# board-a24-color.net
KiCad netlist of a schematic drawn in EasyEDA Pro
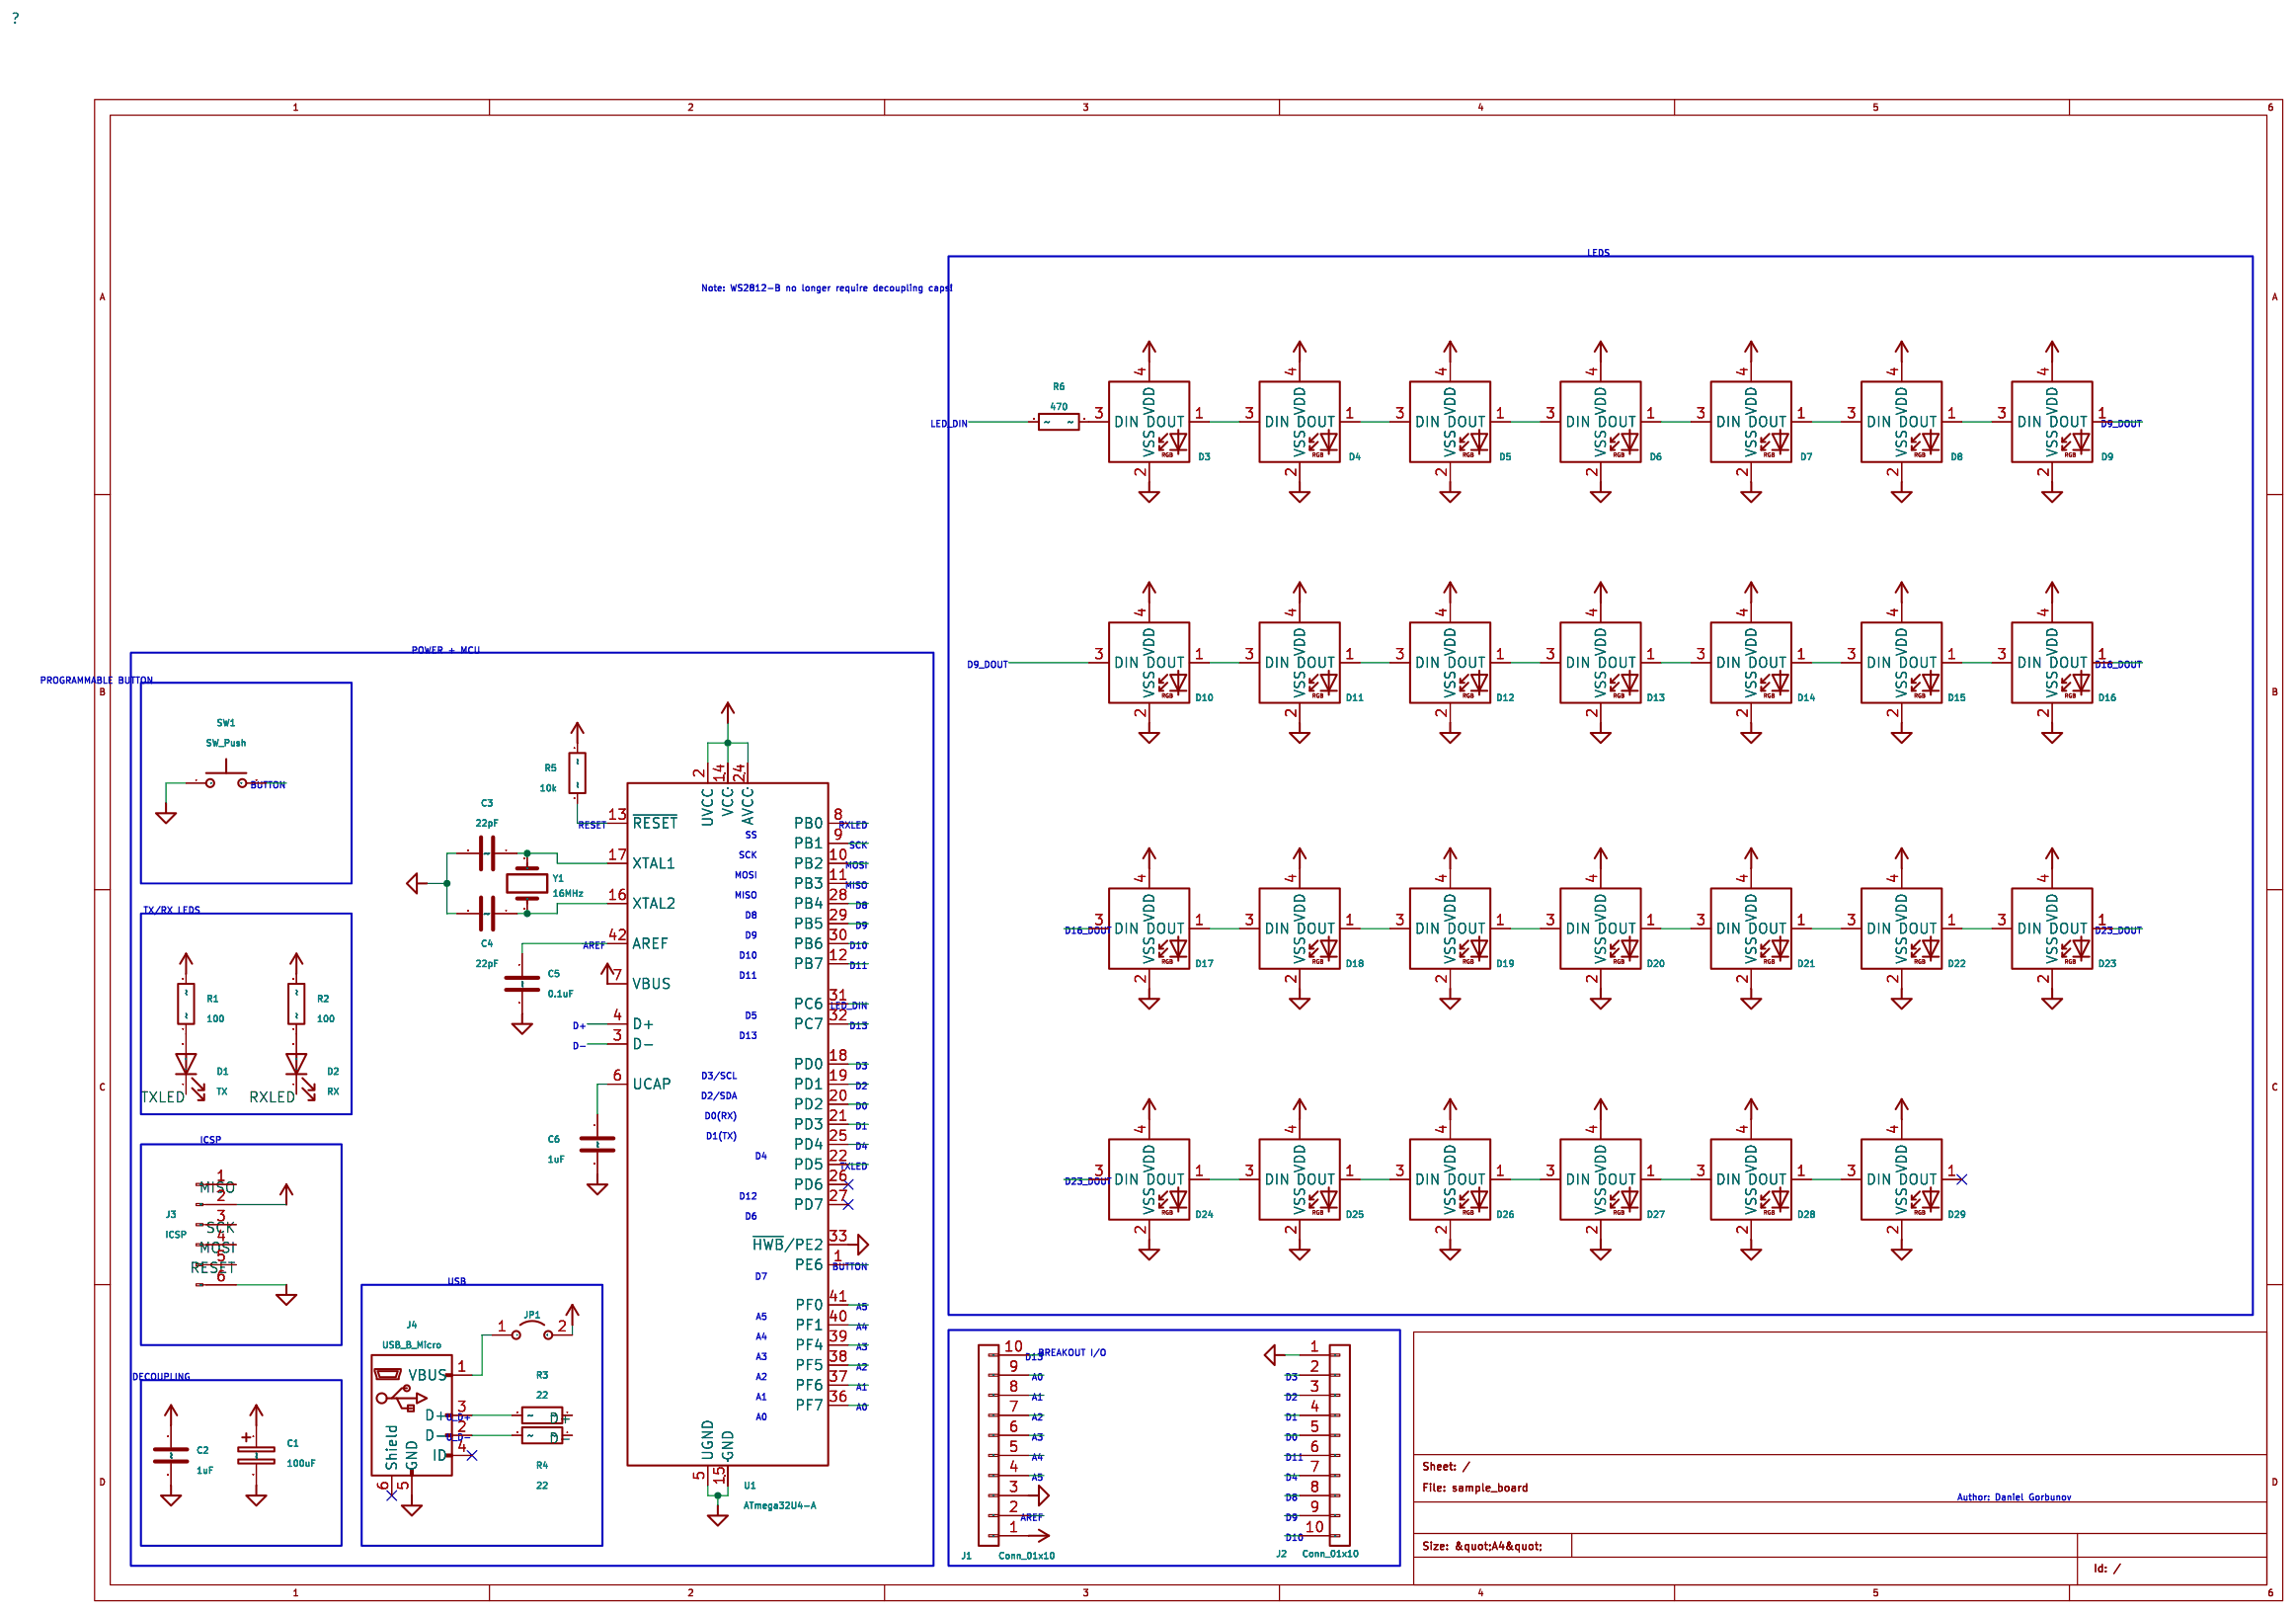
[diagram p0: schematic sheet]

(export (version "E")
  (design (tool "Eeschema 10.0.6"))
  (components
    (comp (ref "C1")
      (value "100uF")
      (footprint "easyedapro:Capacitor_SMD:CP_Elec_5x5.3")
      (libsource (lib "easyedapro") (part "Device_C_Polarized"))
    )
    (comp (ref "C2")
      (value "1uF")
      (footprint "easyedapro:Capacitor_SMD:C_0805_2012Metric_Pad1.18x1.45mm_HandSolder")
      (libsource (lib "easyedapro") (part "Device_C"))
    )
    (comp (ref "C3")
      (value "22pF")
      (footprint "easyedapro:Capacitor_SMD:C_0805_2012Metric_Pad1.18x1.45mm_HandSolder")
      (libsource (lib "easyedapro") (part "Device_C"))
    )
    (comp (ref "C4")
      (value "22pF")
      (footprint "easyedapro:Capacitor_SMD:C_0805_2012Metric_Pad1.18x1.45mm_HandSolder")
      (libsource (lib "easyedapro") (part "Device_C"))
    )
    (comp (ref "C5")
      (value "0.1uF")
      (footprint "easyedapro:Capacitor_SMD:C_0805_2012Metric_Pad1.18x1.45mm_HandSolder")
      (libsource (lib "easyedapro") (part "Device_C"))
    )
    (comp (ref "C6")
      (value "1uF")
      (footprint "easyedapro:Capacitor_SMD:C_0805_2012Metric_Pad1.18x1.45mm_HandSolder")
      (libsource (lib "easyedapro") (part "Device_C"))
    )
    (comp (ref "D1")
      (value "TX")
      (footprint "easyedapro:LED_SMD:LED_0805_2012Metric_Pad1.15x1.40mm_HandSolder")
      (libsource (lib "easyedapro") (part "Device_LED"))
    )
    (comp (ref "D2")
      (value "RX")
      (footprint "easyedapro:LED_SMD:LED_0805_2012Metric_Pad1.15x1.40mm_HandSolder")
      (libsource (lib "easyedapro") (part "Device_LED"))
    )
    (comp (ref "D3")
      (value "SK6812MINI")
      (footprint "easyedapro:LED_SMD:LED_SK6812MINI_PLCC4_3.5x3.5mm_P1.75mm")
      (libsource (lib "easyedapro") (part "LED_SK6812MINI"))
    )
    (comp (ref "D4")
      (value "SK6812MINI")
      (footprint "easyedapro:LED_SMD:LED_SK6812MINI_PLCC4_3.5x3.5mm_P1.75mm")
      (libsource (lib "easyedapro") (part "LED_SK6812MINI"))
    )
    (comp (ref "D5")
      (value "SK6812MINI")
      (footprint "easyedapro:LED_SMD:LED_SK6812MINI_PLCC4_3.5x3.5mm_P1.75mm")
      (libsource (lib "easyedapro") (part "LED_SK6812MINI"))
    )
    (comp (ref "D6")
      (value "SK6812MINI")
      (footprint "easyedapro:LED_SMD:LED_SK6812MINI_PLCC4_3.5x3.5mm_P1.75mm")
      (libsource (lib "easyedapro") (part "LED_SK6812MINI"))
    )
    (comp (ref "D7")
      (value "SK6812MINI")
      (footprint "easyedapro:LED_SMD:LED_SK6812MINI_PLCC4_3.5x3.5mm_P1.75mm")
      (libsource (lib "easyedapro") (part "LED_SK6812MINI"))
    )
    (comp (ref "D8")
      (value "SK6812MINI")
      (footprint "easyedapro:LED_SMD:LED_SK6812MINI_PLCC4_3.5x3.5mm_P1.75mm")
      (libsource (lib "easyedapro") (part "LED_SK6812MINI"))
    )
    (comp (ref "D9")
      (value "SK6812MINI")
      (footprint "easyedapro:LED_SMD:LED_SK6812MINI_PLCC4_3.5x3.5mm_P1.75mm")
      (libsource (lib "easyedapro") (part "LED_SK6812MINI"))
    )
    (comp (ref "D10")
      (value "SK6812MINI")
      (footprint "easyedapro:LED_SMD:LED_SK6812MINI_PLCC4_3.5x3.5mm_P1.75mm")
      (libsource (lib "easyedapro") (part "LED_SK6812MINI"))
    )
    (comp (ref "D11")
      (value "SK6812MINI")
      (footprint "easyedapro:LED_SMD:LED_SK6812MINI_PLCC4_3.5x3.5mm_P1.75mm")
      (libsource (lib "easyedapro") (part "LED_SK6812MINI"))
    )
    (comp (ref "D12")
      (value "SK6812MINI")
      (footprint "easyedapro:LED_SMD:LED_SK6812MINI_PLCC4_3.5x3.5mm_P1.75mm")
      (libsource (lib "easyedapro") (part "LED_SK6812MINI"))
    )
    (comp (ref "D13")
      (value "SK6812MINI")
      (footprint "easyedapro:LED_SMD:LED_SK6812MINI_PLCC4_3.5x3.5mm_P1.75mm")
      (libsource (lib "easyedapro") (part "LED_SK6812MINI"))
    )
    (comp (ref "D14")
      (value "SK6812MINI")
      (footprint "easyedapro:LED_SMD:LED_SK6812MINI_PLCC4_3.5x3.5mm_P1.75mm")
      (libsource (lib "easyedapro") (part "LED_SK6812MINI"))
    )
    (comp (ref "D15")
      (value "SK6812MINI")
      (footprint "easyedapro:LED_SMD:LED_SK6812MINI_PLCC4_3.5x3.5mm_P1.75mm")
      (libsource (lib "easyedapro") (part "LED_SK6812MINI"))
    )
    (comp (ref "D16")
      (value "SK6812MINI")
      (footprint "easyedapro:LED_SMD:LED_SK6812MINI_PLCC4_3.5x3.5mm_P1.75mm")
      (libsource (lib "easyedapro") (part "LED_SK6812MINI"))
    )
    (comp (ref "D17")
      (value "SK6812MINI")
      (footprint "easyedapro:LED_SMD:LED_SK6812MINI_PLCC4_3.5x3.5mm_P1.75mm")
      (libsource (lib "easyedapro") (part "LED_SK6812MINI"))
    )
    (comp (ref "D18")
      (value "SK6812MINI")
      (footprint "easyedapro:LED_SMD:LED_SK6812MINI_PLCC4_3.5x3.5mm_P1.75mm")
      (libsource (lib "easyedapro") (part "LED_SK6812MINI"))
    )
    (comp (ref "D19")
      (value "SK6812MINI")
      (footprint "easyedapro:LED_SMD:LED_SK6812MINI_PLCC4_3.5x3.5mm_P1.75mm")
      (libsource (lib "easyedapro") (part "LED_SK6812MINI"))
    )
    (comp (ref "D20")
      (value "SK6812MINI")
      (footprint "easyedapro:LED_SMD:LED_SK6812MINI_PLCC4_3.5x3.5mm_P1.75mm")
      (libsource (lib "easyedapro") (part "LED_SK6812MINI"))
    )
    (comp (ref "D21")
      (value "SK6812MINI")
      (footprint "easyedapro:LED_SMD:LED_SK6812MINI_PLCC4_3.5x3.5mm_P1.75mm")
      (libsource (lib "easyedapro") (part "LED_SK6812MINI"))
    )
    (comp (ref "D22")
      (value "SK6812MINI")
      (footprint "easyedapro:LED_SMD:LED_SK6812MINI_PLCC4_3.5x3.5mm_P1.75mm")
      (libsource (lib "easyedapro") (part "LED_SK6812MINI"))
    )
    (comp (ref "D23")
      (value "SK6812MINI")
      (footprint "easyedapro:LED_SMD:LED_SK6812MINI_PLCC4_3.5x3.5mm_P1.75mm")
      (libsource (lib "easyedapro") (part "LED_SK6812MINI"))
    )
    (comp (ref "D24")
      (value "SK6812MINI")
      (footprint "easyedapro:LED_SMD:LED_SK6812MINI_PLCC4_3.5x3.5mm_P1.75mm")
      (libsource (lib "easyedapro") (part "LED_SK6812MINI"))
    )
    (comp (ref "D25")
      (value "SK6812MINI")
      (footprint "easyedapro:LED_SMD:LED_SK6812MINI_PLCC4_3.5x3.5mm_P1.75mm")
      (libsource (lib "easyedapro") (part "LED_SK6812MINI"))
    )
    (comp (ref "D26")
      (value "SK6812MINI")
      (footprint "easyedapro:LED_SMD:LED_SK6812MINI_PLCC4_3.5x3.5mm_P1.75mm")
      (libsource (lib "easyedapro") (part "LED_SK6812MINI"))
    )
    (comp (ref "D27")
      (value "SK6812MINI")
      (footprint "easyedapro:LED_SMD:LED_SK6812MINI_PLCC4_3.5x3.5mm_P1.75mm")
      (libsource (lib "easyedapro") (part "LED_SK6812MINI"))
    )
    (comp (ref "D28")
      (value "SK6812MINI")
      (footprint "easyedapro:LED_SMD:LED_SK6812MINI_PLCC4_3.5x3.5mm_P1.75mm")
      (libsource (lib "easyedapro") (part "LED_SK6812MINI"))
    )
    (comp (ref "D29")
      (value "SK6812MINI")
      (footprint "easyedapro:LED_SMD:LED_SK6812MINI_PLCC4_3.5x3.5mm_P1.75mm")
      (libsource (lib "easyedapro") (part "LED_SK6812MINI"))
    )
    (comp (ref "J1")
      (value "Conn_01x10")
      (footprint "easyedapro:Connector_PinHeader_2.54mm:PinHeader_1x10_P2.54mm_Vertical")
      (libsource (lib "easyedapro") (part "Connector_Generic_Conn_01x10"))
    )
    (comp (ref "J2")
      (value "Conn_01x10")
      (footprint "easyedapro:Connector_PinHeader_2.54mm:PinHeader_1x10_P2.54mm_Vertical")
      (libsource (lib "easyedapro") (part "Connector_Generic_Conn_01x10"))
    )
    (comp (ref "J3")
      (value "ICSP")
      (footprint "easyedapro:Connector_PinHeader_2.54mm:PinHeader_2x03_P2.54mm_Vertical")
      (libsource (lib "easyedapro") (part "Connector_Conn_01x06_Pin"))
    )
    (comp (ref "J4")
      (value "USB_B_Micro")
      (footprint "easyedapro:Connector_USB:USB_Micro-B_GCT_USB3076-30-A")
      (libsource (lib "easyedapro") (part "Connector_USB_B_Micro"))
    )
    (comp (ref "JP1")
      (value "Jumper_2_Open")
      (footprint "easyedapro:Jumper:SolderJumper-2_P1.3mm_Open_TrianglePad1.0x1.5mm")
      (libsource (lib "easyedapro") (part "Jumper_Jumper_2_Open"))
    )
    (comp (ref "R1")
      (value "100")
      (footprint "easyedapro:Resistor_SMD:R_0805_2012Metric_Pad1.20x1.40mm_HandSolder")
      (libsource (lib "easyedapro") (part "Device_R"))
    )
    (comp (ref "R2")
      (value "100")
      (footprint "easyedapro:Resistor_SMD:R_0805_2012Metric_Pad1.20x1.40mm_HandSolder")
      (libsource (lib "easyedapro") (part "Device_R"))
    )
    (comp (ref "R3")
      (value "22")
      (footprint "easyedapro:Resistor_SMD:R_0805_2012Metric_Pad1.20x1.40mm_HandSolder")
      (libsource (lib "easyedapro") (part "Device_R"))
    )
    (comp (ref "R4")
      (value "22")
      (footprint "easyedapro:Resistor_SMD:R_0805_2012Metric_Pad1.20x1.40mm_HandSolder")
      (libsource (lib "easyedapro") (part "Device_R"))
    )
    (comp (ref "R5")
      (value "10k")
      (footprint "easyedapro:Resistor_SMD:R_0805_2012Metric_Pad1.20x1.40mm_HandSolder")
      (libsource (lib "easyedapro") (part "Device_R"))
    )
    (comp (ref "R6")
      (value "470")
      (footprint "easyedapro:Resistor_SMD:R_0805_2012Metric_Pad1.20x1.40mm_HandSolder")
      (libsource (lib "easyedapro") (part "Device_R"))
    )
    (comp (ref "SW1")
      (value "SW_Push")
      (footprint "easyedapro:Button_Switch_SMD:SW_SPST_PTS647_Sx38")
      (description "Push button switch, generic, two pins")
      (libsource (lib "easyedapro") (part "Switch_SW_Push"))
    )
    (comp (ref "U1")
      (value "ATmega32U4-A")
      (footprint "easyedapro:Package_QFP:TQFP-44_10x10mm_P0.8mm")
      (libsource (lib "easyedapro") (part "MCU_Microchip_ATmega_ATmega32U4-A"))
    )
    (comp (ref "Y1")
      (value "16MHz")
      (footprint "easyedapro:Crystal:Crystal_SMD_5032-2Pin_5.0x3.2mm")
      (libsource (lib "easyedapro") (part "Device_Crystal"))
    )
  )
  (nets
    (net (code "1") (name "/A0") (class "Default")
      (node (ref "J1") (pin "9") (pinfunction "Pin_9_9") (pintype "unspecified"))
      (node (ref "U1") (pin "36") (pinfunction "PF7_36") (pintype "bidirectional"))
    )
    (net (code "2") (name "/A1") (class "Default")
      (node (ref "J1") (pin "8") (pinfunction "Pin_8_8") (pintype "unspecified"))
      (node (ref "U1") (pin "37") (pinfunction "PF6_37") (pintype "bidirectional"))
    )
    (net (code "3") (name "/A2") (class "Default")
      (node (ref "J1") (pin "7") (pinfunction "Pin_7_7") (pintype "unspecified"))
      (node (ref "U1") (pin "38") (pinfunction "PF5_38") (pintype "bidirectional"))
    )
    (net (code "4") (name "/A3") (class "Default")
      (node (ref "J1") (pin "6") (pinfunction "Pin_6_6") (pintype "unspecified"))
      (node (ref "U1") (pin "39") (pinfunction "PF4_39") (pintype "bidirectional"))
    )
    (net (code "5") (name "/A4") (class "Default")
      (node (ref "J1") (pin "5") (pinfunction "Pin_5_5") (pintype "unspecified"))
      (node (ref "U1") (pin "40") (pinfunction "PF1_40") (pintype "bidirectional"))
    )
    (net (code "6") (name "/A5") (class "Default")
      (node (ref "J1") (pin "4") (pinfunction "Pin_4_4") (pintype "unspecified"))
      (node (ref "U1") (pin "41") (pinfunction "PF0_41") (pintype "bidirectional"))
    )
    (net (code "7") (name "/AREF") (class "Default")
      (node (ref "C5") (pin "1") (pinfunction "~_1") (pintype "unspecified"))
      (node (ref "J1") (pin "2") (pinfunction "Pin_2_2") (pintype "unspecified"))
      (node (ref "U1") (pin "42") (pinfunction "AREF_42") (pintype "unspecified"))
    )
    (net (code "8") (name "/BUTTON") (class "Default")
      (node (ref "SW1") (pin "2") (pinfunction "2_2") (pintype "unspecified"))
      (node (ref "U1") (pin "1") (pinfunction "PE6_1") (pintype "bidirectional"))
    )
    (net (code "9") (name "/D+") (class "Default")
      (node (ref "R3") (pin "1") (pinfunction "~_1") (pintype "unspecified"))
      (node (ref "U1") (pin "4") (pinfunction "D+_4") (pintype "bidirectional"))
    )
    (net (code "10") (name "/D-") (class "Default")
      (node (ref "R4") (pin "1") (pinfunction "~_1") (pintype "unspecified"))
      (node (ref "U1") (pin "3") (pinfunction "D-_3") (pintype "bidirectional"))
    )
    (net (code "11") (name "/D0") (class "Default")
      (node (ref "J2") (pin "5") (pinfunction "Pin_5_5") (pintype "unspecified"))
      (node (ref "U1") (pin "20") (pinfunction "PD2_20") (pintype "bidirectional"))
    )
    (net (code "12") (name "/D1") (class "Default")
      (node (ref "J2") (pin "4") (pinfunction "Pin_4_4") (pintype "unspecified"))
      (node (ref "U1") (pin "21") (pinfunction "PD3_21") (pintype "bidirectional"))
    )
    (net (code "13") (name "/D2") (class "Default")
      (node (ref "J2") (pin "3") (pinfunction "Pin_3_3") (pintype "unspecified"))
      (node (ref "U1") (pin "19") (pinfunction "PD1_19") (pintype "bidirectional"))
    )
    (net (code "14") (name "/D3") (class "Default")
      (node (ref "J2") (pin "2") (pinfunction "Pin_2_2") (pintype "unspecified"))
      (node (ref "U1") (pin "18") (pinfunction "PD0_18") (pintype "bidirectional"))
    )
    (net (code "15") (name "/D4") (class "Default")
      (node (ref "J2") (pin "7") (pinfunction "Pin_7_7") (pintype "unspecified"))
      (node (ref "U1") (pin "25") (pinfunction "PD4_25") (pintype "bidirectional"))
    )
    (net (code "16") (name "/D8") (class "Default")
      (node (ref "J2") (pin "8") (pinfunction "Pin_8_8") (pintype "unspecified"))
      (node (ref "U1") (pin "28") (pinfunction "PB4_28") (pintype "bidirectional"))
    )
    (net (code "17") (name "/D9") (class "Default")
      (node (ref "J2") (pin "9") (pinfunction "Pin_9_9") (pintype "unspecified"))
      (node (ref "U1") (pin "29") (pinfunction "PB5_29") (pintype "bidirectional"))
    )
    (net (code "18") (name "/D9_DOUT") (class "Default")
      (node (ref "D10") (pin "3") (pinfunction "DIN_3") (pintype "input"))
      (node (ref "D9") (pin "1") (pinfunction "DOUT_1") (pintype "output"))
    )
    (net (code "19") (name "/D10") (class "Default")
      (node (ref "J2") (pin "10") (pinfunction "Pin_10_10") (pintype "unspecified"))
      (node (ref "U1") (pin "30") (pinfunction "PB6_30") (pintype "bidirectional"))
    )
    (net (code "20") (name "/D11") (class "Default")
      (node (ref "J2") (pin "6") (pinfunction "Pin_6_6") (pintype "unspecified"))
      (node (ref "U1") (pin "12") (pinfunction "PB7_12") (pintype "bidirectional"))
    )
    (net (code "21") (name "/D13") (class "Default")
      (node (ref "J1") (pin "10") (pinfunction "Pin_10_10") (pintype "unspecified"))
      (node (ref "U1") (pin "32") (pinfunction "PC7_32") (pintype "bidirectional"))
    )
    (net (code "22") (name "/D16_DOUT") (class "Default")
      (node (ref "D16") (pin "1") (pinfunction "DOUT_1") (pintype "output"))
      (node (ref "D17") (pin "3") (pinfunction "DIN_3") (pintype "input"))
    )
    (net (code "23") (name "/D23_DOUT") (class "Default")
      (node (ref "D23") (pin "1") (pinfunction "DOUT_1") (pintype "output"))
      (node (ref "D24") (pin "3") (pinfunction "DIN_3") (pintype "input"))
    )
    (net (code "24") (name "/LED_DIN") (class "Default")
      (node (ref "R6") (pin "1") (pinfunction "~_1") (pintype "unspecified"))
      (node (ref "U1") (pin "31") (pinfunction "PC6_31") (pintype "bidirectional"))
    )
    (net (code "25") (name "/MISO") (class "Default")
      (node (ref "J3") (pin "1") (pinfunction "Pin_1_1") (pintype "unspecified"))
      (node (ref "U1") (pin "11") (pinfunction "PB3_11") (pintype "bidirectional"))
    )
    (net (code "26") (name "/MOSI") (class "Default")
      (node (ref "J3") (pin "4") (pinfunction "Pin_4_4") (pintype "unspecified"))
      (node (ref "U1") (pin "10") (pinfunction "PB2_10") (pintype "bidirectional"))
    )
    (net (code "27") (name "/RESET") (class "Default")
      (node (ref "J3") (pin "5") (pinfunction "Pin_5_5") (pintype "unspecified"))
      (node (ref "R5") (pin "2") (pinfunction "~_2") (pintype "unspecified"))
      (node (ref "U1") (pin "13") (pinfunction "~{RESET}_13") (pintype "input"))
    )
    (net (code "28") (name "/RXLED") (class "Default")
      (node (ref "D2") (pin "1") (pinfunction "K_1") (pintype "unspecified"))
      (node (ref "U1") (pin "8") (pinfunction "PB0_8") (pintype "bidirectional"))
    )
    (net (code "29") (name "/SCK") (class "Default")
      (node (ref "J3") (pin "3") (pinfunction "Pin_3_3") (pintype "unspecified"))
      (node (ref "U1") (pin "9") (pinfunction "PB1_9") (pintype "bidirectional"))
    )
    (net (code "30") (name "/TXLED") (class "Default")
      (node (ref "D1") (pin "1") (pinfunction "K_1") (pintype "unspecified"))
      (node (ref "U1") (pin "22") (pinfunction "PD5_22") (pintype "bidirectional"))
    )
    (net (code "31") (name "/U_D+") (class "Default")
      (node (ref "J4") (pin "3") (pinfunction "D+_3") (pintype "bidirectional"))
      (node (ref "R3") (pin "2") (pinfunction "~_2") (pintype "unspecified"))
    )
    (net (code "32") (name "/U_D-") (class "Default")
      (node (ref "J4") (pin "2") (pinfunction "D-_2") (pintype "bidirectional"))
      (node (ref "R4") (pin "2") (pinfunction "~_2") (pintype "unspecified"))
    )
    (net (code "33") (name "Net-(D1-A)") (class "Default")
      (node (ref "D1") (pin "2") (pinfunction "A_2") (pintype "unspecified"))
      (node (ref "R1") (pin "1") (pinfunction "~_1") (pintype "unspecified"))
    )
    (net (code "34") (name "Net-(D2-A)") (class "Default")
      (node (ref "D2") (pin "2") (pinfunction "A_2") (pintype "unspecified"))
      (node (ref "R2") (pin "1") (pinfunction "~_1") (pintype "unspecified"))
    )
    (net (code "35") (name "Net-(D3-DIN)") (class "Default")
      (node (ref "D3") (pin "3") (pinfunction "DIN_3") (pintype "input"))
      (node (ref "R6") (pin "2") (pinfunction "~_2") (pintype "unspecified"))
    )
    (net (code "36") (name "Net-(D3-DOUT)") (class "Default")
      (node (ref "D3") (pin "1") (pinfunction "DOUT_1") (pintype "output"))
      (node (ref "D4") (pin "3") (pinfunction "DIN_3") (pintype "input"))
    )
    (net (code "37") (name "Net-(D4-DOUT)") (class "Default")
      (node (ref "D4") (pin "1") (pinfunction "DOUT_1") (pintype "output"))
      (node (ref "D5") (pin "3") (pinfunction "DIN_3") (pintype "input"))
    )
    (net (code "38") (name "Net-(D5-DOUT)") (class "Default")
      (node (ref "D5") (pin "1") (pinfunction "DOUT_1") (pintype "output"))
      (node (ref "D6") (pin "3") (pinfunction "DIN_3") (pintype "input"))
    )
    (net (code "39") (name "Net-(D6-DOUT)") (class "Default")
      (node (ref "D6") (pin "1") (pinfunction "DOUT_1") (pintype "output"))
      (node (ref "D7") (pin "3") (pinfunction "DIN_3") (pintype "input"))
    )
    (net (code "40") (name "Net-(D7-DOUT)") (class "Default")
      (node (ref "D7") (pin "1") (pinfunction "DOUT_1") (pintype "output"))
      (node (ref "D8") (pin "3") (pinfunction "DIN_3") (pintype "input"))
    )
    (net (code "41") (name "Net-(D8-DOUT)") (class "Default")
      (node (ref "D8") (pin "1") (pinfunction "DOUT_1") (pintype "output"))
      (node (ref "D9") (pin "3") (pinfunction "DIN_3") (pintype "input"))
    )
    (net (code "42") (name "Net-(D10-DOUT)") (class "Default")
      (node (ref "D10") (pin "1") (pinfunction "DOUT_1") (pintype "output"))
      (node (ref "D11") (pin "3") (pinfunction "DIN_3") (pintype "input"))
    )
    (net (code "43") (name "Net-(D11-DOUT)") (class "Default")
      (node (ref "D11") (pin "1") (pinfunction "DOUT_1") (pintype "output"))
      (node (ref "D12") (pin "3") (pinfunction "DIN_3") (pintype "input"))
    )
    (net (code "44") (name "Net-(D12-DOUT)") (class "Default")
      (node (ref "D12") (pin "1") (pinfunction "DOUT_1") (pintype "output"))
      (node (ref "D13") (pin "3") (pinfunction "DIN_3") (pintype "input"))
    )
    (net (code "45") (name "Net-(D13-DOUT)") (class "Default")
      (node (ref "D13") (pin "1") (pinfunction "DOUT_1") (pintype "output"))
      (node (ref "D14") (pin "3") (pinfunction "DIN_3") (pintype "input"))
    )
    (net (code "46") (name "Net-(D14-DOUT)") (class "Default")
      (node (ref "D14") (pin "1") (pinfunction "DOUT_1") (pintype "output"))
      (node (ref "D15") (pin "3") (pinfunction "DIN_3") (pintype "input"))
    )
    (net (code "47") (name "Net-(D15-DOUT)") (class "Default")
      (node (ref "D15") (pin "1") (pinfunction "DOUT_1") (pintype "output"))
      (node (ref "D16") (pin "3") (pinfunction "DIN_3") (pintype "input"))
    )
    (net (code "48") (name "Net-(D17-DOUT)") (class "Default")
      (node (ref "D17") (pin "1") (pinfunction "DOUT_1") (pintype "output"))
      (node (ref "D18") (pin "3") (pinfunction "DIN_3") (pintype "input"))
    )
    (net (code "49") (name "Net-(D18-DOUT)") (class "Default")
      (node (ref "D18") (pin "1") (pinfunction "DOUT_1") (pintype "output"))
      (node (ref "D19") (pin "3") (pinfunction "DIN_3") (pintype "input"))
    )
    (net (code "50") (name "Net-(D19-DOUT)") (class "Default")
      (node (ref "D19") (pin "1") (pinfunction "DOUT_1") (pintype "output"))
      (node (ref "D20") (pin "3") (pinfunction "DIN_3") (pintype "input"))
    )
    (net (code "51") (name "Net-(D20-DOUT)") (class "Default")
      (node (ref "D20") (pin "1") (pinfunction "DOUT_1") (pintype "output"))
      (node (ref "D21") (pin "3") (pinfunction "DIN_3") (pintype "input"))
    )
    (net (code "52") (name "Net-(D21-DOUT)") (class "Default")
      (node (ref "D21") (pin "1") (pinfunction "DOUT_1") (pintype "output"))
      (node (ref "D22") (pin "3") (pinfunction "DIN_3") (pintype "input"))
    )
    (net (code "53") (name "Net-(D22-DOUT)") (class "Default")
      (node (ref "D22") (pin "1") (pinfunction "DOUT_1") (pintype "output"))
      (node (ref "D23") (pin "3") (pinfunction "DIN_3") (pintype "input"))
    )
    (net (code "54") (name "Net-(D24-DOUT)") (class "Default")
      (node (ref "D24") (pin "1") (pinfunction "DOUT_1") (pintype "output"))
      (node (ref "D25") (pin "3") (pinfunction "DIN_3") (pintype "input"))
    )
    (net (code "55") (name "Net-(D25-DOUT)") (class "Default")
      (node (ref "D25") (pin "1") (pinfunction "DOUT_1") (pintype "output"))
      (node (ref "D26") (pin "3") (pinfunction "DIN_3") (pintype "input"))
    )
    (net (code "56") (name "Net-(D26-DOUT)") (class "Default")
      (node (ref "D26") (pin "1") (pinfunction "DOUT_1") (pintype "output"))
      (node (ref "D27") (pin "3") (pinfunction "DIN_3") (pintype "input"))
    )
    (net (code "57") (name "Net-(D27-DOUT)") (class "Default")
      (node (ref "D27") (pin "1") (pinfunction "DOUT_1") (pintype "output"))
      (node (ref "D28") (pin "3") (pinfunction "DIN_3") (pintype "input"))
    )
    (net (code "58") (name "Net-(D28-DOUT)") (class "Default")
      (node (ref "D28") (pin "1") (pinfunction "DOUT_1") (pintype "output"))
      (node (ref "D29") (pin "3") (pinfunction "DIN_3") (pintype "input"))
    )
    (net (code "59") (name "Net-(J4-VBUS)") (class "Default")
      (node (ref "J4") (pin "1") (pinfunction "VBUS_1") (pintype "unspecified"))
      (node (ref "JP1") (pin "1") (pinfunction "A_1") (pintype "unspecified"))
    )
    (net (code "60") (name "Net-(U1-UCAP)") (class "Default")
      (node (ref "C6") (pin "1") (pinfunction "~_1") (pintype "unspecified"))
      (node (ref "U1") (pin "6") (pinfunction "UCAP_6") (pintype "unspecified"))
    )
    (net (code "61") (name "Net-(U1-XTAL1)") (class "Default")
      (node (ref "C3") (pin "1") (pinfunction "~_1") (pintype "unspecified"))
      (node (ref "U1") (pin "17") (pinfunction "XTAL1_17") (pintype "input"))
      (node (ref "Y1") (pin "1") (pinfunction "1_1") (pintype "unspecified"))
    )
    (net (code "62") (name "Net-(U1-XTAL2)") (class "Default")
      (node (ref "C4") (pin "1") (pinfunction "~_1") (pintype "unspecified"))
      (node (ref "U1") (pin "16") (pinfunction "XTAL2_16") (pintype "output"))
      (node (ref "Y1") (pin "2") (pinfunction "2_2") (pintype "unspecified"))
    )
    (net (code "63") (name "POWER_+5V") (class "Default")
      (node (ref "C1") (pin "1") (pinfunction "~_1") (pintype "unspecified"))
      (node (ref "C2") (pin "1") (pinfunction "~_1") (pintype "unspecified"))
      (node (ref "D10") (pin "4") (pinfunction "VDD_4") (pintype "unspecified"))
      (node (ref "D11") (pin "4") (pinfunction "VDD_4") (pintype "unspecified"))
      (node (ref "D12") (pin "4") (pinfunction "VDD_4") (pintype "unspecified"))
      (node (ref "D13") (pin "4") (pinfunction "VDD_4") (pintype "unspecified"))
      (node (ref "D14") (pin "4") (pinfunction "VDD_4") (pintype "unspecified"))
      (node (ref "D15") (pin "4") (pinfunction "VDD_4") (pintype "unspecified"))
      (node (ref "D16") (pin "4") (pinfunction "VDD_4") (pintype "unspecified"))
      (node (ref "D17") (pin "4") (pinfunction "VDD_4") (pintype "unspecified"))
      (node (ref "D18") (pin "4") (pinfunction "VDD_4") (pintype "unspecified"))
      (node (ref "D19") (pin "4") (pinfunction "VDD_4") (pintype "unspecified"))
      (node (ref "D20") (pin "4") (pinfunction "VDD_4") (pintype "unspecified"))
      (node (ref "D21") (pin "4") (pinfunction "VDD_4") (pintype "unspecified"))
      (node (ref "D22") (pin "4") (pinfunction "VDD_4") (pintype "unspecified"))
      (node (ref "D23") (pin "4") (pinfunction "VDD_4") (pintype "unspecified"))
      (node (ref "D24") (pin "4") (pinfunction "VDD_4") (pintype "unspecified"))
      (node (ref "D25") (pin "4") (pinfunction "VDD_4") (pintype "unspecified"))
      (node (ref "D26") (pin "4") (pinfunction "VDD_4") (pintype "unspecified"))
      (node (ref "D27") (pin "4") (pinfunction "VDD_4") (pintype "unspecified"))
      (node (ref "D28") (pin "4") (pinfunction "VDD_4") (pintype "unspecified"))
      (node (ref "D29") (pin "4") (pinfunction "VDD_4") (pintype "unspecified"))
      (node (ref "D3") (pin "4") (pinfunction "VDD_4") (pintype "unspecified"))
      (node (ref "D4") (pin "4") (pinfunction "VDD_4") (pintype "unspecified"))
      (node (ref "D5") (pin "4") (pinfunction "VDD_4") (pintype "unspecified"))
      (node (ref "D6") (pin "4") (pinfunction "VDD_4") (pintype "unspecified"))
      (node (ref "D7") (pin "4") (pinfunction "VDD_4") (pintype "unspecified"))
      (node (ref "D8") (pin "4") (pinfunction "VDD_4") (pintype "unspecified"))
      (node (ref "D9") (pin "4") (pinfunction "VDD_4") (pintype "unspecified"))
      (node (ref "J1") (pin "1") (pinfunction "Pin_1_1") (pintype "unspecified"))
      (node (ref "J3") (pin "2") (pinfunction "Pin_2_2") (pintype "unspecified"))
      (node (ref "JP1") (pin "2") (pinfunction "B_2") (pintype "unspecified"))
      (node (ref "R1") (pin "2") (pinfunction "~_2") (pintype "unspecified"))
      (node (ref "R2") (pin "2") (pinfunction "~_2") (pintype "unspecified"))
      (node (ref "R5") (pin "1") (pinfunction "~_1") (pintype "unspecified"))
      (node (ref "U1") (pin "14") (pinfunction "VCC_14") (pintype "unspecified"))
      (node (ref "U1") (pin "2") (pinfunction "UVCC_2") (pintype "unspecified"))
      (node (ref "U1") (pin "24") (pinfunction "AVCC_24") (pintype "unspecified"))
      (node (ref "U1") (pin "34") (pinfunction "VCC_34") (pintype "unspecified"))
      (node (ref "U1") (pin "44") (pinfunction "AVCC_44") (pintype "unspecified"))
      (node (ref "U1") (pin "7") (pinfunction "VBUS_7") (pintype "input"))
    )
    (net (code "64") (name "POWER_GND") (class "Default")
      (node (ref "C1") (pin "2") (pinfunction "~_2") (pintype "unspecified"))
      (node (ref "C2") (pin "2") (pinfunction "~_2") (pintype "unspecified"))
      (node (ref "C3") (pin "2") (pinfunction "~_2") (pintype "unspecified"))
      (node (ref "C4") (pin "2") (pinfunction "~_2") (pintype "unspecified"))
      (node (ref "C5") (pin "2") (pinfunction "~_2") (pintype "unspecified"))
      (node (ref "C6") (pin "2") (pinfunction "~_2") (pintype "unspecified"))
      (node (ref "D10") (pin "2") (pinfunction "VSS_2") (pintype "unspecified"))
      (node (ref "D11") (pin "2") (pinfunction "VSS_2") (pintype "unspecified"))
      (node (ref "D12") (pin "2") (pinfunction "VSS_2") (pintype "unspecified"))
      (node (ref "D13") (pin "2") (pinfunction "VSS_2") (pintype "unspecified"))
      (node (ref "D14") (pin "2") (pinfunction "VSS_2") (pintype "unspecified"))
      (node (ref "D15") (pin "2") (pinfunction "VSS_2") (pintype "unspecified"))
      (node (ref "D16") (pin "2") (pinfunction "VSS_2") (pintype "unspecified"))
      (node (ref "D17") (pin "2") (pinfunction "VSS_2") (pintype "unspecified"))
      (node (ref "D18") (pin "2") (pinfunction "VSS_2") (pintype "unspecified"))
      (node (ref "D19") (pin "2") (pinfunction "VSS_2") (pintype "unspecified"))
      (node (ref "D20") (pin "2") (pinfunction "VSS_2") (pintype "unspecified"))
      (node (ref "D21") (pin "2") (pinfunction "VSS_2") (pintype "unspecified"))
      (node (ref "D22") (pin "2") (pinfunction "VSS_2") (pintype "unspecified"))
      (node (ref "D23") (pin "2") (pinfunction "VSS_2") (pintype "unspecified"))
      (node (ref "D24") (pin "2") (pinfunction "VSS_2") (pintype "unspecified"))
      (node (ref "D25") (pin "2") (pinfunction "VSS_2") (pintype "unspecified"))
      (node (ref "D26") (pin "2") (pinfunction "VSS_2") (pintype "unspecified"))
      (node (ref "D27") (pin "2") (pinfunction "VSS_2") (pintype "unspecified"))
      (node (ref "D28") (pin "2") (pinfunction "VSS_2") (pintype "unspecified"))
      (node (ref "D29") (pin "2") (pinfunction "VSS_2") (pintype "unspecified"))
      (node (ref "D3") (pin "2") (pinfunction "VSS_2") (pintype "unspecified"))
      (node (ref "D4") (pin "2") (pinfunction "VSS_2") (pintype "unspecified"))
      (node (ref "D5") (pin "2") (pinfunction "VSS_2") (pintype "unspecified"))
      (node (ref "D6") (pin "2") (pinfunction "VSS_2") (pintype "unspecified"))
      (node (ref "D7") (pin "2") (pinfunction "VSS_2") (pintype "unspecified"))
      (node (ref "D8") (pin "2") (pinfunction "VSS_2") (pintype "unspecified"))
      (node (ref "D9") (pin "2") (pinfunction "VSS_2") (pintype "unspecified"))
      (node (ref "J1") (pin "3") (pinfunction "Pin_3_3") (pintype "unspecified"))
      (node (ref "J2") (pin "1") (pinfunction "Pin_1_1") (pintype "unspecified"))
      (node (ref "J3") (pin "6") (pinfunction "Pin_6_6") (pintype "unspecified"))
      (node (ref "J4") (pin "5") (pinfunction "GND_5") (pintype "unspecified"))
      (node (ref "SW1") (pin "1") (pinfunction "1_1") (pintype "unspecified"))
      (node (ref "U1") (pin "15") (pinfunction "GND_15") (pintype "unspecified"))
      (node (ref "U1") (pin "23") (pinfunction "GND_23") (pintype "unspecified"))
      (node (ref "U1") (pin "33") (pinfunction "~{HWB}/PE2_33") (pintype "bidirectional"))
      (node (ref "U1") (pin "35") (pinfunction "GND_35") (pintype "unspecified"))
      (node (ref "U1") (pin "43") (pinfunction "GND_43") (pintype "unspecified"))
      (node (ref "U1") (pin "5") (pinfunction "UGND_5") (pintype "unspecified"))
    )
    (net (code "65") (name "unconnected-(D29-DOUT-Pad1)") (class "Default")
      (node (ref "D29") (pin "1") (pinfunction "DOUT_1") (pintype "output+no_connect"))
    )
    (net (code "66") (name "unconnected-(J4-ID-Pad4)") (class "Default")
      (node (ref "J4") (pin "4") (pinfunction "ID_4") (pintype "unspecified+no_connect"))
    )
    (net (code "67") (name "unconnected-(J4-Shield-Pad6)") (class "Default")
      (node (ref "J4") (pin "6") (pinfunction "Shield_6") (pintype "unspecified+no_connect"))
    )
    (net (code "68") (name "unconnected-(U1-PD6-Pad26)") (class "Default")
      (node (ref "U1") (pin "26") (pinfunction "PD6_26") (pintype "bidirectional+no_connect"))
    )
    (net (code "69") (name "unconnected-(U1-PD7-Pad27)") (class "Default")
      (node (ref "U1") (pin "27") (pinfunction "PD7_27") (pintype "bidirectional+no_connect"))
    )
  )
)
